# new_esplay.net
KiCad netlist of a schematic drawn in EAGLE
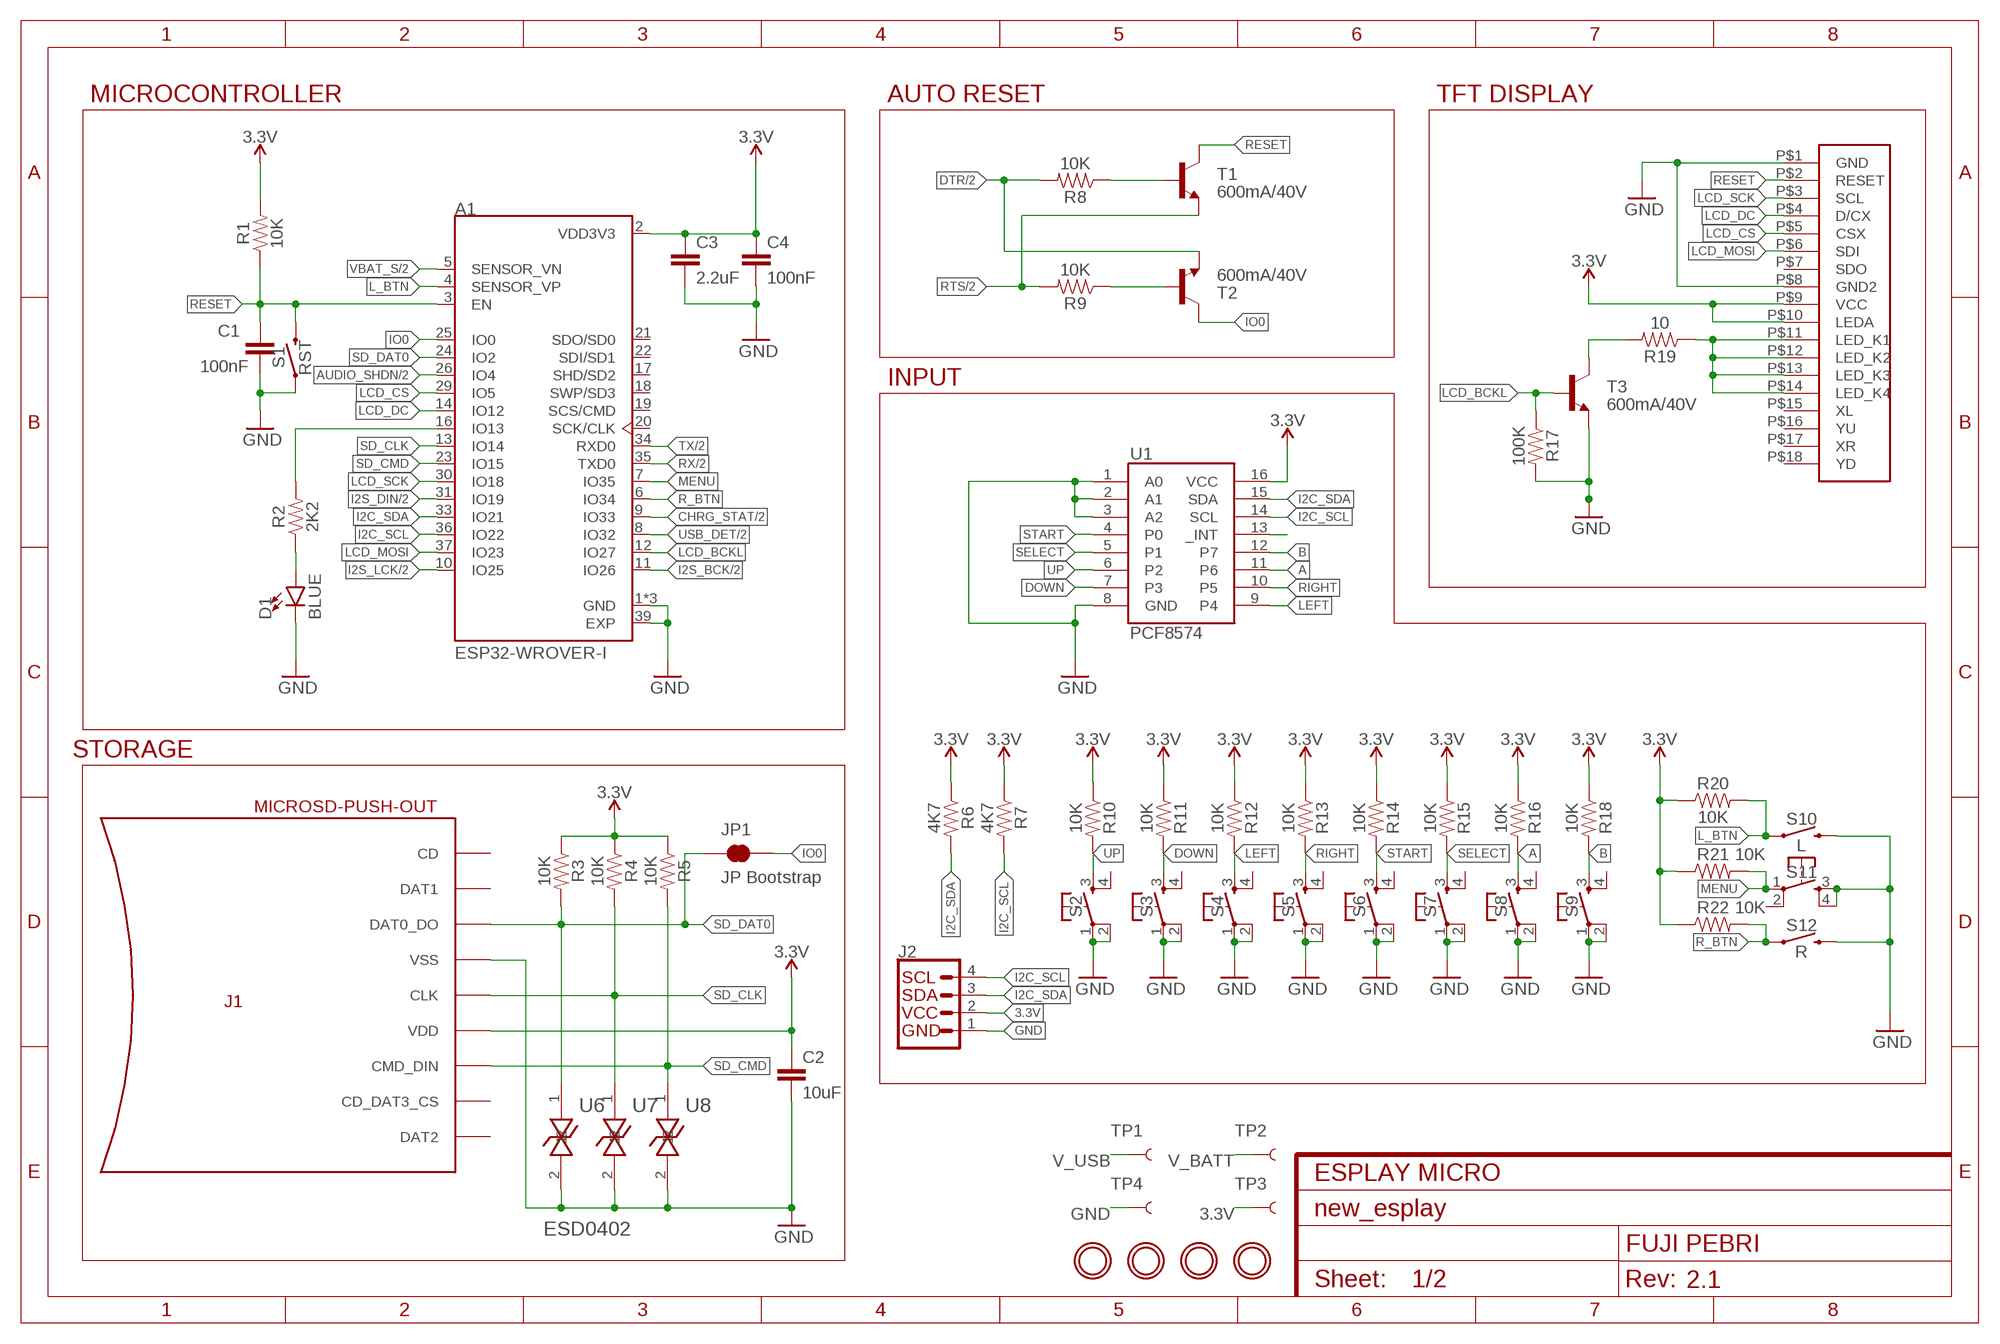
[diagram p0: schematic, sheet 1]
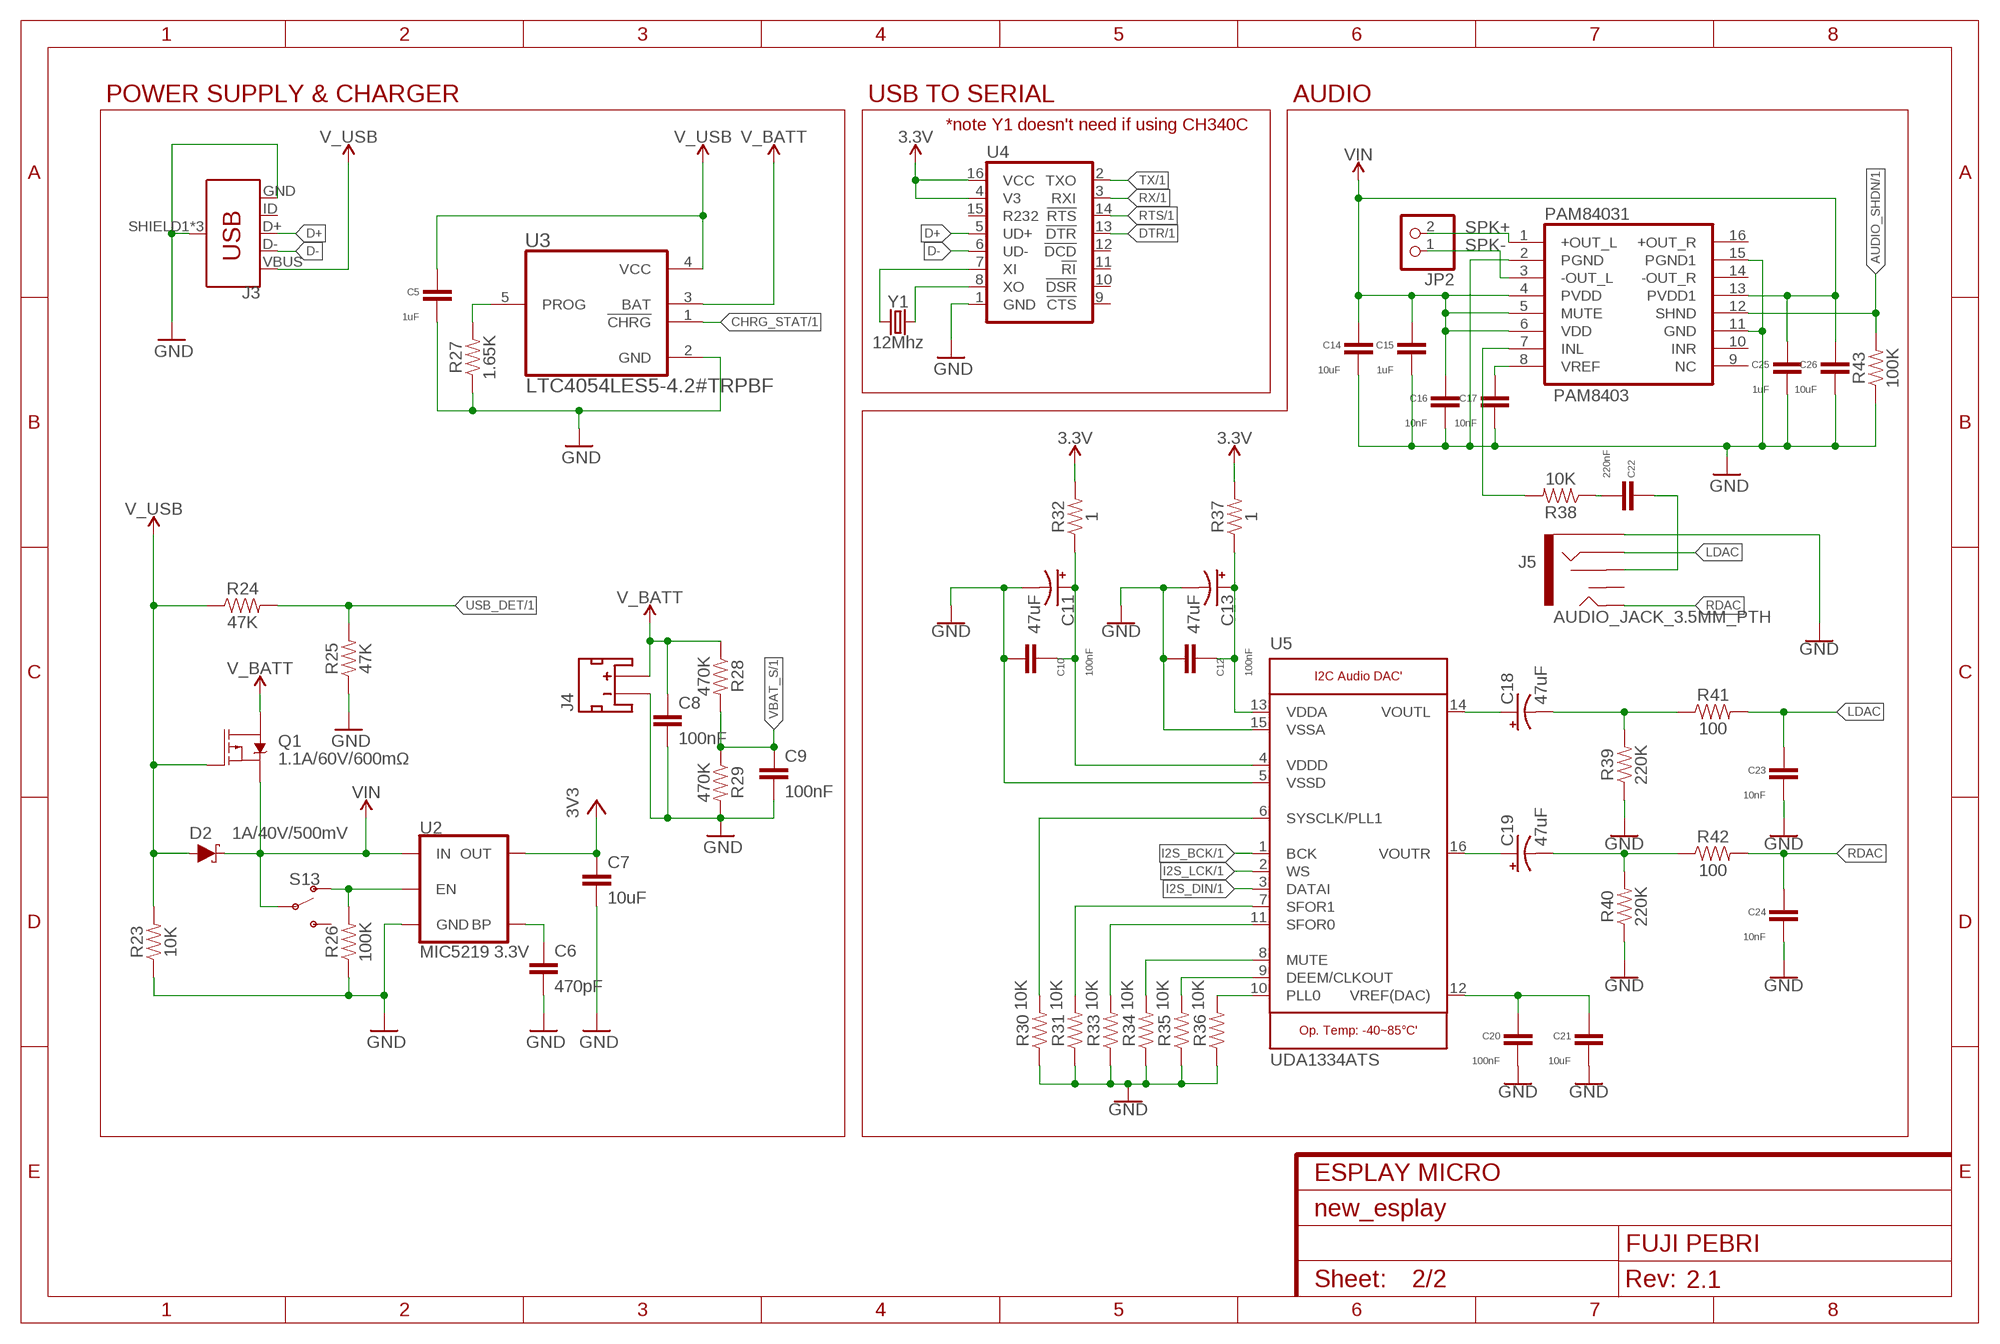
[diagram p1: schematic, sheet 2]

(export (version "E")
  (design (tool "Eeschema 10.0.6"))
  (components
    (comp (ref "A1")
      (value "ESP32-WROVER-I")
      (footprint "eagle-import:XCVR_ESP32-WROVER-I")
      (fields (field (name "MF") "Espressif Systems"))
      (libsource (lib "eagle-import") (part "ESP32-WROVER-I"))
    )
    (comp (ref "C1")
      (value "100nF")
      (footprint "eagle-import:0805")
      (libsource (lib "eagle-import") (part "2.2UF-0805-25V-(+80/-20%)"))
    )
    (comp (ref "C2")
      (value "10uF")
      (footprint "eagle-import:0805")
      (libsource (lib "eagle-import") (part "2.2UF-0805-25V-(+80/-20%)"))
    )
    (comp (ref "C3")
      (value "2.2uF")
      (footprint "eagle-import:0805")
      (libsource (lib "eagle-import") (part "2.2UF-0805-25V-(+80/-20%)"))
    )
    (comp (ref "C4")
      (value "100nF")
      (footprint "eagle-import:0805")
      (libsource (lib "eagle-import") (part "2.2UF-0805-25V-(+80/-20%)"))
    )
    (comp (ref "D1")
      (value "BLUE")
      (footprint "eagle-import:LED-0603")
      (libsource (lib "eagle-import") (part "LED-BLUE0603"))
    )
    (comp (ref "H1")
      (value "MICROBUILDER_MOUNTINGHOLE3.0THIN")
      (footprint "eagle-import:MICROBUILDER_MOUNTINGHOLE_3.0_PLATEDTHIN")
      (libsource (lib "eagle-import") (part "MICROBUILDER_MOUNTINGHOLE3.0THIN"))
    )
    (comp (ref "H2")
      (value "MICROBUILDER_MOUNTINGHOLE3.0THIN")
      (footprint "eagle-import:MICROBUILDER_MOUNTINGHOLE_3.0_PLATEDTHIN")
      (libsource (lib "eagle-import") (part "MICROBUILDER_MOUNTINGHOLE3.0THIN"))
    )
    (comp (ref "H3")
      (value "MICROBUILDER_MOUNTINGHOLE3.0THIN")
      (footprint "eagle-import:MICROBUILDER_MOUNTINGHOLE_3.0_PLATEDTHIN")
      (libsource (lib "eagle-import") (part "MICROBUILDER_MOUNTINGHOLE3.0THIN"))
    )
    (comp (ref "H4")
      (value "MICROBUILDER_MOUNTINGHOLE3.0THIN")
      (footprint "eagle-import:MICROBUILDER_MOUNTINGHOLE_3.0_PLATEDTHIN")
      (libsource (lib "eagle-import") (part "MICROBUILDER_MOUNTINGHOLE3.0THIN"))
    )
    (comp (ref "J1")
      (value "MICROSD-PUSH-OUT")
      (footprint "eagle-import:MICROSD-PUSH-OUT")
      (libsource (lib "eagle-import") (part "MICROSD-PUSH-OUT"))
    )
    (comp (ref "J2")
      (value "QWIIC_CONNECTORJS-1MM")
      (footprint "eagle-import:1X04_1MM_RA")
      (libsource (lib "eagle-import") (part "QWIIC_CONNECTORJS-1MM"))
    )
    (comp (ref "JP1")
      (value "JP Bootstrap")
      (footprint "eagle-import:SMT-JUMPER_2_NC_TRACE_NO-SILK")
      (libsource (lib "eagle-import") (part "JUMPER-SMT_2_NC_TRACE_NO-SILK"))
    )
    (comp (ref "LCD1")
      (value "ILI9341-2.4")
      (footprint "eagle-import:ILI9341-2.4")
      (libsource (lib "eagle-import") (part "ILI9341-2.4"))
    )
    (comp (ref "R1")
      (value "10K")
      (footprint "eagle-import:0805")
      (libsource (lib "eagle-import") (part "0.22OHM-0805-1/4W-1%"))
    )
    (comp (ref "R2")
      (value "2K2")
      (footprint "eagle-import:0805")
      (libsource (lib "eagle-import") (part "0.22OHM-0805-1/4W-1%"))
    )
    (comp (ref "R3")
      (value "10K")
      (footprint "eagle-import:0805")
      (libsource (lib "eagle-import") (part "0.22OHM-0805-1/4W-1%"))
    )
    (comp (ref "R4")
      (value "10K")
      (footprint "eagle-import:0805")
      (libsource (lib "eagle-import") (part "0.22OHM-0805-1/4W-1%"))
    )
    (comp (ref "R5")
      (value "10K")
      (footprint "eagle-import:0805")
      (libsource (lib "eagle-import") (part "0.22OHM-0805-1/4W-1%"))
    )
    (comp (ref "R6")
      (value "4K7")
      (footprint "eagle-import:0805")
      (libsource (lib "eagle-import") (part "0.22OHM-0805-1/4W-1%"))
    )
    (comp (ref "R7")
      (value "4K7")
      (footprint "eagle-import:0805")
      (libsource (lib "eagle-import") (part "0.22OHM-0805-1/4W-1%"))
    )
    (comp (ref "R8")
      (value "10K")
      (footprint "eagle-import:0805")
      (libsource (lib "eagle-import") (part "0.22OHM-0805-1/4W-1%"))
    )
    (comp (ref "R9")
      (value "10K")
      (footprint "eagle-import:0805")
      (libsource (lib "eagle-import") (part "0.22OHM-0805-1/4W-1%"))
    )
    (comp (ref "R10")
      (value "10K")
      (footprint "eagle-import:0805")
      (libsource (lib "eagle-import") (part "0.22OHM-0805-1/4W-1%"))
    )
    (comp (ref "R11")
      (value "10K")
      (footprint "eagle-import:0805")
      (libsource (lib "eagle-import") (part "0.22OHM-0805-1/4W-1%"))
    )
    (comp (ref "R12")
      (value "10K")
      (footprint "eagle-import:0805")
      (libsource (lib "eagle-import") (part "0.22OHM-0805-1/4W-1%"))
    )
    (comp (ref "R13")
      (value "10K")
      (footprint "eagle-import:0805")
      (libsource (lib "eagle-import") (part "0.22OHM-0805-1/4W-1%"))
    )
    (comp (ref "R14")
      (value "10K")
      (footprint "eagle-import:0805")
      (libsource (lib "eagle-import") (part "0.22OHM-0805-1/4W-1%"))
    )
    (comp (ref "R15")
      (value "10K")
      (footprint "eagle-import:0805")
      (libsource (lib "eagle-import") (part "0.22OHM-0805-1/4W-1%"))
    )
    (comp (ref "R16")
      (value "10K")
      (footprint "eagle-import:0805")
      (libsource (lib "eagle-import") (part "0.22OHM-0805-1/4W-1%"))
    )
    (comp (ref "R17")
      (value "100K")
      (footprint "eagle-import:0805")
      (libsource (lib "eagle-import") (part "0.22OHM-0805-1/4W-1%"))
    )
    (comp (ref "R18")
      (value "10K")
      (footprint "eagle-import:0805")
      (libsource (lib "eagle-import") (part "0.22OHM-0805-1/4W-1%"))
    )
    (comp (ref "R19")
      (value "10")
      (footprint "eagle-import:0805")
      (libsource (lib "eagle-import") (part "0.22OHM-0805-1/4W-1%"))
    )
    (comp (ref "R20")
      (value "10K")
      (footprint "eagle-import:0805")
      (libsource (lib "eagle-import") (part "0.22OHM-0805-1/4W-1%"))
    )
    (comp (ref "R21")
      (value "10K")
      (footprint "eagle-import:0805")
      (libsource (lib "eagle-import") (part "0.22OHM-0805-1/4W-1%"))
    )
    (comp (ref "R22")
      (value "10K")
      (footprint "eagle-import:0805")
      (libsource (lib "eagle-import") (part "0.22OHM-0805-1/4W-1%"))
    )
    (comp (ref "S1")
      (value "RST")
      (footprint "eagle-import:TACTILE_SWITCH_SMD_4.6X2.8MM")
      (libsource (lib "eagle-import") (part "MOMENTARY-SWITCH-SPST-SMD-4.6X2.8MM"))
    )
    (comp (ref "S2")
      (value "MOMENTARY-SWITCH-SPST-2-SMD-5.2MM")
      (footprint "eagle-import:TACTILE_SWITCH_SMD_5.2MM")
      (libsource (lib "eagle-import") (part "MOMENTARY-SWITCH-SPST-2-SMD-5.2MM"))
    )
    (comp (ref "S3")
      (value "MOMENTARY-SWITCH-SPST-2-SMD-5.2MM")
      (footprint "eagle-import:TACTILE_SWITCH_SMD_5.2MM")
      (libsource (lib "eagle-import") (part "MOMENTARY-SWITCH-SPST-2-SMD-5.2MM"))
    )
    (comp (ref "S4")
      (value "MOMENTARY-SWITCH-SPST-2-SMD-5.2MM")
      (footprint "eagle-import:TACTILE_SWITCH_SMD_5.2MM")
      (libsource (lib "eagle-import") (part "MOMENTARY-SWITCH-SPST-2-SMD-5.2MM"))
    )
    (comp (ref "S5")
      (value "MOMENTARY-SWITCH-SPST-2-SMD-5.2MM")
      (footprint "eagle-import:TACTILE_SWITCH_SMD_5.2MM")
      (libsource (lib "eagle-import") (part "MOMENTARY-SWITCH-SPST-2-SMD-5.2MM"))
    )
    (comp (ref "S6")
      (value "MOMENTARY-SWITCH-SPST-2-SMD-5.2MM")
      (footprint "eagle-import:TACTILE_SWITCH_SMD_5.2MM")
      (libsource (lib "eagle-import") (part "MOMENTARY-SWITCH-SPST-2-SMD-5.2MM"))
    )
    (comp (ref "S7")
      (value "MOMENTARY-SWITCH-SPST-2-SMD-5.2MM")
      (footprint "eagle-import:TACTILE_SWITCH_SMD_5.2MM")
      (libsource (lib "eagle-import") (part "MOMENTARY-SWITCH-SPST-2-SMD-5.2MM"))
    )
    (comp (ref "S8")
      (value "MOMENTARY-SWITCH-SPST-2-SMD-5.2MM")
      (footprint "eagle-import:TACTILE_SWITCH_SMD_5.2MM")
      (libsource (lib "eagle-import") (part "MOMENTARY-SWITCH-SPST-2-SMD-5.2MM"))
    )
    (comp (ref "S9")
      (value "MOMENTARY-SWITCH-SPST-2-SMD-5.2MM")
      (footprint "eagle-import:TACTILE_SWITCH_SMD_5.2MM")
      (libsource (lib "eagle-import") (part "MOMENTARY-SWITCH-SPST-2-SMD-5.2MM"))
    )
    (comp (ref "S10")
      (value "L")
      (footprint "eagle-import:TACTILE_SWITCH_PTH_RIGHT_ANGLE_KIT")
      (libsource (lib "eagle-import") (part "MOMENTARY-SWITCH-SPST-PTH-RIGHT-ANGLE-KIT"))
    )
    (comp (ref "S11")
      (value "MOMENTARY-SWITCH-SPST-2-SMD-5.2MM")
      (footprint "eagle-import:TACTILE_SWITCH_SMD_5.2MM")
      (libsource (lib "eagle-import") (part "MOMENTARY-SWITCH-SPST-2-SMD-5.2MM"))
    )
    (comp (ref "S12")
      (value "R")
      (footprint "eagle-import:TACTILE_SWITCH_PTH_RIGHT_ANGLE_KIT")
      (libsource (lib "eagle-import") (part "MOMENTARY-SWITCH-SPST-PTH-RIGHT-ANGLE-KIT"))
    )
    (comp (ref "T1")
      (value "600mA/40V")
      (footprint "eagle-import:SOT23-3")
      (libsource (lib "eagle-import") (part "TRANS_NPN-MMBT2222AL"))
    )
    (comp (ref "T2")
      (value "600mA/40V")
      (footprint "eagle-import:SOT23-3")
      (libsource (lib "eagle-import") (part "TRANS_NPN-MMBT2222AL"))
    )
    (comp (ref "T3")
      (value "600mA/40V")
      (footprint "eagle-import:SOT23-3")
      (libsource (lib "eagle-import") (part "TRANS_NPN-MMBT2222AL"))
    )
    (comp (ref "TP1")
      (value "TEST-POINT3")
      (footprint "eagle-import:PAD.03X.03")
      (libsource (lib "eagle-import") (part "TEST-POINT3"))
    )
    (comp (ref "TP2")
      (value "TEST-POINT3")
      (footprint "eagle-import:PAD.03X.03")
      (libsource (lib "eagle-import") (part "TEST-POINT3"))
    )
    (comp (ref "TP3")
      (value "TEST-POINT3")
      (footprint "eagle-import:PAD.03X.03")
      (libsource (lib "eagle-import") (part "TEST-POINT3"))
    )
    (comp (ref "TP4")
      (value "TEST-POINT3")
      (footprint "eagle-import:PAD.03X.03")
      (libsource (lib "eagle-import") (part "TEST-POINT3"))
    )
    (comp (ref "U1")
      (value "PCF8574")
      (footprint "eagle-import:SO16")
      (fields (field (name "MF") "Texas Instruments"))
      (libsource (lib "eagle-import") (part "PCF8574"))
    )
    (comp (ref "U6")
      (value "ESD0402")
      (footprint "eagle-import:ESD0402")
      (libsource (lib "eagle-import") (part "ESD0402"))
    )
    (comp (ref "U7")
      (value "ESD0402")
      (footprint "eagle-import:ESD0402")
      (libsource (lib "eagle-import") (part "ESD0402"))
    )
    (comp (ref "U8")
      (value "ESD0402")
      (footprint "eagle-import:ESD0402")
      (libsource (lib "eagle-import") (part "ESD0402"))
    )
    (comp (ref "C5")
      (value "1uF")
      (footprint "eagle-import:0805")
      (libsource (lib "eagle-import") (part "2.2UF-0805-25V-(+80/-20%)"))
    )
    (comp (ref "C6")
      (value "470pF")
      (footprint "eagle-import:0805")
      (libsource (lib "eagle-import") (part "2.2UF-0805-25V-(+80/-20%)"))
    )
    (comp (ref "C7")
      (value "10uF")
      (footprint "eagle-import:0805")
      (libsource (lib "eagle-import") (part "2.2UF-0805-25V-(+80/-20%)"))
    )
    (comp (ref "C8")
      (value "100nF")
      (footprint "eagle-import:0805")
      (libsource (lib "eagle-import") (part "2.2UF-0805-25V-(+80/-20%)"))
    )
    (comp (ref "C9")
      (value "100nF")
      (footprint "eagle-import:0805")
      (libsource (lib "eagle-import") (part "2.2UF-0805-25V-(+80/-20%)"))
    )
    (comp (ref "C10")
      (value "100nF")
      (footprint "eagle-import:0805")
      (libsource (lib "eagle-import") (part "2.2UF-0805-25V-(+80/-20%)"))
    )
    (comp (ref "C11")
      (value "47uF")
      (footprint "eagle-import:EIA3528")
      (libsource (lib "eagle-import") (part "47UF-POLAR-EIA3528-10V-10%"))
    )
    (comp (ref "C12")
      (value "100nF")
      (footprint "eagle-import:0805")
      (libsource (lib "eagle-import") (part "2.2UF-0805-25V-(+80/-20%)"))
    )
    (comp (ref "C13")
      (value "47uF")
      (footprint "eagle-import:EIA3528")
      (libsource (lib "eagle-import") (part "47UF-POLAR-EIA3528-10V-10%"))
    )
    (comp (ref "C14")
      (value "10uF")
      (footprint "eagle-import:0805")
      (libsource (lib "eagle-import") (part "2.2UF-0805-25V-(+80/-20%)"))
    )
    (comp (ref "C15")
      (value "1uF")
      (footprint "eagle-import:0805")
      (libsource (lib "eagle-import") (part "2.2UF-0805-25V-(+80/-20%)"))
    )
    (comp (ref "C16")
      (value "10nF")
      (footprint "eagle-import:0805")
      (libsource (lib "eagle-import") (part "2.2UF-0805-25V-(+80/-20%)"))
    )
    (comp (ref "C17")
      (value "10nF")
      (footprint "eagle-import:0805")
      (libsource (lib "eagle-import") (part "2.2UF-0805-25V-(+80/-20%)"))
    )
    (comp (ref "C18")
      (value "47uF")
      (footprint "eagle-import:EIA3528")
      (libsource (lib "eagle-import") (part "47UF-POLAR-EIA3528-10V-10%"))
    )
    (comp (ref "C19")
      (value "47uF")
      (footprint "eagle-import:EIA3528")
      (libsource (lib "eagle-import") (part "47UF-POLAR-EIA3528-10V-10%"))
    )
    (comp (ref "C20")
      (value "100nF")
      (footprint "eagle-import:0805")
      (libsource (lib "eagle-import") (part "2.2UF-0805-25V-(+80/-20%)"))
    )
    (comp (ref "C21")
      (value "10uF")
      (footprint "eagle-import:0805")
      (libsource (lib "eagle-import") (part "2.2UF-0805-25V-(+80/-20%)"))
    )
    (comp (ref "C22")
      (value "220nF")
      (footprint "eagle-import:0805")
      (libsource (lib "eagle-import") (part "2.2UF-0805-25V-(+80/-20%)"))
    )
    (comp (ref "C23")
      (value "10nF")
      (footprint "eagle-import:0805")
      (libsource (lib "eagle-import") (part "2.2UF-0805-25V-(+80/-20%)"))
    )
    (comp (ref "C24")
      (value "10nF")
      (footprint "eagle-import:0805")
      (libsource (lib "eagle-import") (part "2.2UF-0805-25V-(+80/-20%)"))
    )
    (comp (ref "C25")
      (value "1uF")
      (footprint "eagle-import:0805")
      (libsource (lib "eagle-import") (part "2.2UF-0805-25V-(+80/-20%)"))
    )
    (comp (ref "C26")
      (value "10uF")
      (footprint "eagle-import:0805")
      (libsource (lib "eagle-import") (part "2.2UF-0805-25V-(+80/-20%)"))
    )
    (comp (ref "D2")
      (value "1A/40V/500mV")
      (footprint "eagle-import:SMA-DIODE")
      (libsource (lib "eagle-import") (part "DIODE-SCHOTTKY-SS14"))
    )
    (comp (ref "J3")
      (value "USB_MICRO-B_FEMALE-SMT")
      (footprint "eagle-import:USB-B-MICRO-SMD")
      (libsource (lib "eagle-import") (part "USB_MICRO-B_FEMALE-SMT"))
    )
    (comp (ref "J4")
      (value "JST_2MM_MALE")
      (footprint "eagle-import:JST-2-SMD")
      (libsource (lib "eagle-import") (part "JST_2MM_MALE"))
    )
    (comp (ref "J5")
      (value "AUDIO_JACK_3.5MM_PTH")
      (footprint "eagle-import:AUDIO-JACK")
      (libsource (lib "eagle-import") (part "AUDIO_JACK_3.5MM_PTH"))
    )
    (comp (ref "JP2")
      (value "PINHD-1X2_2.00")
      (footprint "eagle-import:1X02M")
      (libsource (lib "eagle-import") (part "PINHD-1X2_2.00"))
    )
    (comp (ref "PAM84031")
      (value "PAM8403")
      (footprint "eagle-import:SOP-16")
      (libsource (lib "eagle-import") (part "PAM8403"))
    )
    (comp (ref "Q1")
      (value "1.1A/60V/600mΩ")
      (footprint "eagle-import:SOT23-3")
      (libsource (lib "eagle-import") (part "MOSFET_PCH-SI2309DS"))
    )
    (comp (ref "R23")
      (value "10K")
      (footprint "eagle-import:0805")
      (libsource (lib "eagle-import") (part "0.22OHM-0805-1/4W-1%"))
    )
    (comp (ref "R24")
      (value "47K")
      (footprint "eagle-import:0805")
      (libsource (lib "eagle-import") (part "0.22OHM-0805-1/4W-1%"))
    )
    (comp (ref "R25")
      (value "47K")
      (footprint "eagle-import:0805")
      (libsource (lib "eagle-import") (part "0.22OHM-0805-1/4W-1%"))
    )
    (comp (ref "R26")
      (value "100K")
      (footprint "eagle-import:0805")
      (libsource (lib "eagle-import") (part "0.22OHM-0805-1/4W-1%"))
    )
    (comp (ref "R27")
      (value "1.65K")
      (footprint "eagle-import:0805")
      (libsource (lib "eagle-import") (part "0.3OHM-0805-1/8W-1%"))
    )
    (comp (ref "R28")
      (value "470K")
      (footprint "eagle-import:0805")
      (libsource (lib "eagle-import") (part "0.22OHM-0805-1/4W-1%"))
    )
    (comp (ref "R29")
      (value "470K")
      (footprint "eagle-import:0805")
      (libsource (lib "eagle-import") (part "0.22OHM-0805-1/4W-1%"))
    )
    (comp (ref "R30")
      (value "10K")
      (footprint "eagle-import:0805")
      (libsource (lib "eagle-import") (part "0.3OHM-0805-1/8W-1%"))
    )
    (comp (ref "R31")
      (value "10K")
      (footprint "eagle-import:0805")
      (libsource (lib "eagle-import") (part "0.3OHM-0805-1/8W-1%"))
    )
    (comp (ref "R32")
      (value "1")
      (footprint "eagle-import:0805")
      (libsource (lib "eagle-import") (part "0.3OHM-0805-1/8W-1%"))
    )
    (comp (ref "R33")
      (value "10K")
      (footprint "eagle-import:0805")
      (libsource (lib "eagle-import") (part "0.3OHM-0805-1/8W-1%"))
    )
    (comp (ref "R34")
      (value "10K")
      (footprint "eagle-import:0805")
      (libsource (lib "eagle-import") (part "0.3OHM-0805-1/8W-1%"))
    )
    (comp (ref "R35")
      (value "10K")
      (footprint "eagle-import:0805")
      (libsource (lib "eagle-import") (part "0.3OHM-0805-1/8W-1%"))
    )
    (comp (ref "R36")
      (value "10K")
      (footprint "eagle-import:0805")
      (libsource (lib "eagle-import") (part "0.3OHM-0805-1/8W-1%"))
    )
    (comp (ref "R37")
      (value "1")
      (footprint "eagle-import:0805")
      (libsource (lib "eagle-import") (part "0.3OHM-0805-1/8W-1%"))
    )
    (comp (ref "R38")
      (value "10K")
      (footprint "eagle-import:0805")
      (libsource (lib "eagle-import") (part "0.3OHM-0805-1/8W-1%"))
    )
    (comp (ref "R39")
      (value "220K")
      (footprint "eagle-import:0805")
      (libsource (lib "eagle-import") (part "0.3OHM-0805-1/8W-1%"))
    )
    (comp (ref "R40")
      (value "220K")
      (footprint "eagle-import:0805")
      (libsource (lib "eagle-import") (part "0.3OHM-0805-1/8W-1%"))
    )
    (comp (ref "R41")
      (value "100")
      (footprint "eagle-import:0805")
      (libsource (lib "eagle-import") (part "0.3OHM-0805-1/8W-1%"))
    )
    (comp (ref "R42")
      (value "100")
      (footprint "eagle-import:0805")
      (libsource (lib "eagle-import") (part "0.3OHM-0805-1/8W-1%"))
    )
    (comp (ref "R43")
      (value "100K")
      (footprint "eagle-import:0805")
      (libsource (lib "eagle-import") (part "0.3OHM-0805-1/8W-1%"))
    )
    (comp (ref "S13")
      (value "SWITCH-SPDT-SMD-RIGHT-ANGLE")
      (footprint "eagle-import:SWITCH_SPST_SMD_A")
      (libsource (lib "eagle-import") (part "SWITCH-SPDT-SMD-RIGHT-ANGLE"))
    )
    (comp (ref "U2")
      (value "MIC5219 3.3V")
      (footprint "eagle-import:SOT23-5")
      (libsource (lib "eagle-import") (part "V_REG_MIC52193.3V"))
    )
    (comp (ref "U3")
      (value "LTC4054LES5-4.2#TRPBF")
      (footprint "eagle-import:SOT95P280X100-5N")
      (fields
        (field (name "DIGI-KEY_PART_NUMBER") "LTC4054LES5-4.2#TRPBFCT-ND")
        (field (name "MF") "Linear Technology/Analog")
      )
      (libsource (lib "eagle-import") (part "LTC4054LES5-4.2#TRPBF"))
    )
    (comp (ref "U4")
      (value "CH340G")
      (footprint "eagle-import:SO016")
      (libsource (lib "eagle-import") (part "CH340GSMD"))
    )
    (comp (ref "U5")
      (value "UDA1334ATS")
      (footprint "eagle-import:MICROBUILDER_SSOP16_4.4MM")
      (libsource (lib "eagle-import") (part "MICROBUILDER_AUDIO_I2S_UDA1334{dblquote}{dblquote}"))
    )
    (comp (ref "Y1")
      (value "12Mhz")
      (footprint "eagle-import:CRYSTAL-SMD-5X3.2-4PAD")
      (libsource (lib "eagle-import") (part "CRYSTALSMD-5X3.2-4PAD"))
    )
  )
  (nets
    (net (code "1") (name "3.3V") (class "Default")
      (node (ref "A1") (pin "2") (pinfunction "VDD3V3_2") (pintype "power_in"))
      (node (ref "C2") (pin "1") (pinfunction "1_1") (pintype "passive"))
      (node (ref "C3") (pin "1") (pinfunction "1_1") (pintype "passive"))
      (node (ref "C4") (pin "1") (pinfunction "1_1") (pintype "passive"))
      (node (ref "C7") (pin "1") (pinfunction "1_1") (pintype "passive"))
      (node (ref "J1") (pin "4") (pinfunction "VDD_4") (pintype "bidirectional"))
      (node (ref "J2") (pin "2") (pinfunction "2_2") (pintype "power_in"))
      (node (ref "LCD1") (pin "P$10") (pinfunction "LEDA_P$10") (pintype "bidirectional"))
      (node (ref "LCD1") (pin "P$9") (pinfunction "VCC_P$9") (pintype "bidirectional"))
      (node (ref "R1") (pin "2") (pinfunction "2_2") (pintype "passive"))
      (node (ref "R10") (pin "1") (pinfunction "1_1") (pintype "passive"))
      (node (ref "R11") (pin "1") (pinfunction "1_1") (pintype "passive"))
      (node (ref "R12") (pin "1") (pinfunction "1_1") (pintype "passive"))
      (node (ref "R13") (pin "1") (pinfunction "1_1") (pintype "passive"))
      (node (ref "R14") (pin "1") (pinfunction "1_1") (pintype "passive"))
      (node (ref "R15") (pin "1") (pinfunction "1_1") (pintype "passive"))
      (node (ref "R16") (pin "1") (pinfunction "1_1") (pintype "passive"))
      (node (ref "R18") (pin "1") (pinfunction "1_1") (pintype "passive"))
      (node (ref "R20") (pin "1") (pinfunction "1_1") (pintype "passive"))
      (node (ref "R21") (pin "1") (pinfunction "1_1") (pintype "passive"))
      (node (ref "R22") (pin "1") (pinfunction "1_1") (pintype "passive"))
      (node (ref "R3") (pin "1") (pinfunction "1_1") (pintype "passive"))
      (node (ref "R32") (pin "2") (pinfunction "2_2") (pintype "passive"))
      (node (ref "R37") (pin "2") (pinfunction "2_2") (pintype "passive"))
      (node (ref "R4") (pin "1") (pinfunction "1_1") (pintype "passive"))
      (node (ref "R5") (pin "1") (pinfunction "1_1") (pintype "passive"))
      (node (ref "R6") (pin "1") (pinfunction "1_1") (pintype "passive"))
      (node (ref "R7") (pin "1") (pinfunction "1_1") (pintype "passive"))
      (node (ref "TP3") (pin "P$1") (pinfunction "1_P$1") (pintype "bidirectional"))
      (node (ref "U1") (pin "16") (pinfunction "VCC_16") (pintype "bidirectional"))
      (node (ref "U2") (pin "5") (pinfunction "OUT_5") (pintype "passive"))
      (node (ref "U4") (pin "16") (pinfunction "VCC_16") (pintype "bidirectional"))
      (node (ref "U4") (pin "4") (pinfunction "V3_4") (pintype "bidirectional"))
    )
    (net (code "2") (name "A") (class "Default")
      (node (ref "R16") (pin "2") (pinfunction "2_2") (pintype "passive"))
      (node (ref "S8") (pin "3") (pinfunction "3_3") (pintype "passive"))
      (node (ref "U1") (pin "11") (pinfunction "P6_11") (pintype "bidirectional"))
    )
    (net (code "3") (name "AUDIO_SHDN") (class "Default")
      (node (ref "A1") (pin "26") (pinfunction "IO4_26") (pintype "bidirectional"))
      (node (ref "PAM84031") (pin "12") (pinfunction "SHND_12") (pintype "output"))
      (node (ref "R43") (pin "2") (pinfunction "2_2") (pintype "passive"))
    )
    (net (code "4") (name "B") (class "Default")
      (node (ref "R18") (pin "2") (pinfunction "2_2") (pintype "passive"))
      (node (ref "S9") (pin "3") (pinfunction "3_3") (pintype "passive"))
      (node (ref "U1") (pin "12") (pinfunction "P7_12") (pintype "bidirectional"))
    )
    (net (code "5") (name "CHRG_STAT") (class "Default")
      (node (ref "A1") (pin "9") (pinfunction "IO33_9") (pintype "bidirectional"))
      (node (ref "U3") (pin "1") (pinfunction "~{CHRG}_1") (pintype "output"))
    )
    (net (code "6") (name "D+") (class "Default")
      (node (ref "J3") (pin "D+") (pinfunction "D+_D+") (pintype "bidirectional"))
      (node (ref "U4") (pin "5") (pinfunction "UD+_5") (pintype "bidirectional"))
    )
    (net (code "7") (name "D-") (class "Default")
      (node (ref "J3") (pin "D-") (pinfunction "D-_D-") (pintype "bidirectional"))
      (node (ref "U4") (pin "6") (pinfunction "UD-_6") (pintype "bidirectional"))
    )
    (net (code "8") (name "DOWN") (class "Default")
      (node (ref "R11") (pin "2") (pinfunction "2_2") (pintype "passive"))
      (node (ref "S3") (pin "3") (pinfunction "3_3") (pintype "passive"))
      (node (ref "U1") (pin "7") (pinfunction "P3_7") (pintype "bidirectional"))
    )
    (net (code "9") (name "DTR") (class "Default")
      (node (ref "R8") (pin "2") (pinfunction "2_2") (pintype "passive"))
      (node (ref "T2") (pin "2") (pinfunction "E_2") (pintype "passive"))
      (node (ref "U4") (pin "13") (pinfunction "~{DTR}_13") (pintype "bidirectional"))
    )
    (net (code "10") (name "GND") (class "Default")
      (node (ref "A1") (pin "1") (pinfunction "GND_1") (pintype "power_in"))
      (node (ref "A1") (pin "15") (pinfunction "GND_15") (pintype "power_in"))
      (node (ref "A1") (pin "38") (pinfunction "GND_38") (pintype "power_in"))
      (node (ref "A1") (pin "39") (pinfunction "EXP_39") (pintype "power_in"))
      (node (ref "C1") (pin "2") (pinfunction "2_2") (pintype "passive"))
      (node (ref "C10") (pin "1") (pinfunction "1_1") (pintype "passive"))
      (node (ref "C11") (pin "C") (pinfunction "-_C") (pintype "passive"))
      (node (ref "C12") (pin "1") (pinfunction "1_1") (pintype "passive"))
      (node (ref "C13") (pin "C") (pinfunction "-_C") (pintype "passive"))
      (node (ref "C14") (pin "1") (pinfunction "1_1") (pintype "passive"))
      (node (ref "C15") (pin "1") (pinfunction "1_1") (pintype "passive"))
      (node (ref "C16") (pin "1") (pinfunction "1_1") (pintype "passive"))
      (node (ref "C17") (pin "1") (pinfunction "1_1") (pintype "passive"))
      (node (ref "C2") (pin "2") (pinfunction "2_2") (pintype "passive"))
      (node (ref "C20") (pin "1") (pinfunction "1_1") (pintype "passive"))
      (node (ref "C21") (pin "1") (pinfunction "1_1") (pintype "passive"))
      (node (ref "C23") (pin "1") (pinfunction "1_1") (pintype "passive"))
      (node (ref "C24") (pin "1") (pinfunction "1_1") (pintype "passive"))
      (node (ref "C25") (pin "1") (pinfunction "1_1") (pintype "passive"))
      (node (ref "C26") (pin "1") (pinfunction "1_1") (pintype "passive"))
      (node (ref "C3") (pin "2") (pinfunction "2_2") (pintype "passive"))
      (node (ref "C4") (pin "2") (pinfunction "2_2") (pintype "passive"))
      (node (ref "C5") (pin "1") (pinfunction "1_1") (pintype "passive"))
      (node (ref "C6") (pin "2") (pinfunction "2_2") (pintype "passive"))
      (node (ref "C7") (pin "2") (pinfunction "2_2") (pintype "passive"))
      (node (ref "C8") (pin "2") (pinfunction "2_2") (pintype "passive"))
      (node (ref "C9") (pin "2") (pinfunction "2_2") (pintype "passive"))
      (node (ref "D1") (pin "C") (pinfunction "C_C") (pintype "passive"))
      (node (ref "J1") (pin "6") (pinfunction "VSS_6") (pintype "bidirectional"))
      (node (ref "J1") (pin "G1") (pinfunction "VSS_G1") (pintype "bidirectional"))
      (node (ref "J1") (pin "G2") (pinfunction "VSS_G2") (pintype "bidirectional"))
      (node (ref "J1") (pin "G3") (pinfunction "VSS_G3") (pintype "bidirectional"))
      (node (ref "J1") (pin "G4") (pinfunction "VSS_G4") (pintype "bidirectional"))
      (node (ref "J2") (pin "1") (pinfunction "1_1") (pintype "power_in"))
      (node (ref "J3") (pin "GND") (pinfunction "GND_GND") (pintype "power_in"))
      (node (ref "J3") (pin "SHIELD1") (pinfunction "SHIELD_SHIELD1") (pintype "bidirectional"))
      (node (ref "J3") (pin "SHIELD2") (pinfunction "SHIELD_SHIELD2") (pintype "bidirectional"))
      (node (ref "J3") (pin "SHIELD3") (pinfunction "SHIELD_SHIELD3") (pintype "bidirectional"))
      (node (ref "J4") (pin "1") (pinfunction "-_1") (pintype "bidirectional"))
      (node (ref "J5") (pin "SLEEVE") (pinfunction "SLEEVE_SLEEVE") (pintype "bidirectional"))
      (node (ref "LCD1") (pin "P$1") (pinfunction "GND_P$1") (pintype "bidirectional"))
      (node (ref "LCD1") (pin "P$8") (pinfunction "GND2_P$8") (pintype "bidirectional"))
      (node (ref "PAM84031") (pin "11") (pinfunction "GND_11") (pintype "output"))
      (node (ref "PAM84031") (pin "15") (pinfunction "PGND1_15") (pintype "output"))
      (node (ref "PAM84031") (pin "2") (pinfunction "PGND_2") (pintype "input"))
      (node (ref "R17") (pin "2") (pinfunction "2_2") (pintype "passive"))
      (node (ref "R23") (pin "1") (pinfunction "1_1") (pintype "passive"))
      (node (ref "R25") (pin "1") (pinfunction "1_1") (pintype "passive"))
      (node (ref "R26") (pin "1") (pinfunction "1_1") (pintype "passive"))
      (node (ref "R27") (pin "1") (pinfunction "1_1") (pintype "passive"))
      (node (ref "R29") (pin "2") (pinfunction "2_2") (pintype "passive"))
      (node (ref "R30") (pin "1") (pinfunction "1_1") (pintype "passive"))
      (node (ref "R31") (pin "1") (pinfunction "1_1") (pintype "passive"))
      (node (ref "R33") (pin "1") (pinfunction "1_1") (pintype "passive"))
      (node (ref "R34") (pin "1") (pinfunction "1_1") (pintype "passive"))
      (node (ref "R35") (pin "1") (pinfunction "1_1") (pintype "passive"))
      (node (ref "R36") (pin "1") (pinfunction "1_1") (pintype "passive"))
      (node (ref "R39") (pin "1") (pinfunction "1_1") (pintype "passive"))
      (node (ref "R40") (pin "1") (pinfunction "1_1") (pintype "passive"))
      (node (ref "R43") (pin "1") (pinfunction "1_1") (pintype "passive"))
      (node (ref "S1") (pin "1") (pinfunction "1_1") (pintype "passive"))
      (node (ref "S1") (pin "2") (pinfunction "1_2") (pintype "passive"))
      (node (ref "S10") (pin "2") (pinfunction "2_2") (pintype "passive"))
      (node (ref "S11") (pin "3") (pinfunction "3_3") (pintype "passive"))
      (node (ref "S11") (pin "4") (pinfunction "4_4") (pintype "passive"))
      (node (ref "S12") (pin "2") (pinfunction "2_2") (pintype "passive"))
      (node (ref "S2") (pin "1") (pinfunction "1_1") (pintype "passive"))
      (node (ref "S2") (pin "2") (pinfunction "2_2") (pintype "passive"))
      (node (ref "S3") (pin "1") (pinfunction "1_1") (pintype "passive"))
      (node (ref "S3") (pin "2") (pinfunction "2_2") (pintype "passive"))
      (node (ref "S4") (pin "1") (pinfunction "1_1") (pintype "passive"))
      (node (ref "S4") (pin "2") (pinfunction "2_2") (pintype "passive"))
      (node (ref "S5") (pin "1") (pinfunction "1_1") (pintype "passive"))
      (node (ref "S5") (pin "2") (pinfunction "2_2") (pintype "passive"))
      (node (ref "S6") (pin "1") (pinfunction "1_1") (pintype "passive"))
      (node (ref "S6") (pin "2") (pinfunction "2_2") (pintype "passive"))
      (node (ref "S7") (pin "1") (pinfunction "1_1") (pintype "passive"))
      (node (ref "S7") (pin "2") (pinfunction "2_2") (pintype "passive"))
      (node (ref "S8") (pin "1") (pinfunction "1_1") (pintype "passive"))
      (node (ref "S8") (pin "2") (pinfunction "2_2") (pintype "passive"))
      (node (ref "S9") (pin "1") (pinfunction "1_1") (pintype "passive"))
      (node (ref "S9") (pin "2") (pinfunction "2_2") (pintype "passive"))
      (node (ref "T3") (pin "2") (pinfunction "E_2") (pintype "passive"))
      (node (ref "TP4") (pin "P$1") (pinfunction "1_P$1") (pintype "bidirectional"))
      (node (ref "U1") (pin "1") (pinfunction "A0_1") (pintype "bidirectional"))
      (node (ref "U1") (pin "2") (pinfunction "A1_2") (pintype "bidirectional"))
      (node (ref "U1") (pin "3") (pinfunction "A2_3") (pintype "bidirectional"))
      (node (ref "U1") (pin "8") (pinfunction "GND_8") (pintype "bidirectional"))
      (node (ref "U2") (pin "2") (pinfunction "GND_2") (pintype "input"))
      (node (ref "U3") (pin "2") (pinfunction "GND_2") (pintype "power_in"))
      (node (ref "U4") (pin "1") (pinfunction "GND_1") (pintype "bidirectional"))
      (node (ref "U5") (pin "15") (pinfunction "VSSA_15") (pintype "power_in"))
      (node (ref "U5") (pin "5") (pinfunction "VSSD_5") (pintype "power_in"))
      (node (ref "U6") (pin "2") (pinfunction "2_2") (pintype "bidirectional"))
      (node (ref "U7") (pin "2") (pinfunction "2_2") (pintype "bidirectional"))
      (node (ref "U8") (pin "2") (pinfunction "2_2") (pintype "bidirectional"))
    )
    (net (code "11") (name "I2C_SCL") (class "Default")
      (node (ref "A1") (pin "36") (pinfunction "IO22_36") (pintype "bidirectional"))
      (node (ref "J2") (pin "4") (pinfunction "4_4") (pintype "passive"))
      (node (ref "R7") (pin "2") (pinfunction "2_2") (pintype "passive"))
      (node (ref "U1") (pin "14") (pinfunction "SCL_14") (pintype "bidirectional"))
    )
    (net (code "12") (name "I2C_SDA") (class "Default")
      (node (ref "A1") (pin "33") (pinfunction "IO21_33") (pintype "bidirectional"))
      (node (ref "J2") (pin "3") (pinfunction "3_3") (pintype "passive"))
      (node (ref "R6") (pin "2") (pinfunction "2_2") (pintype "passive"))
      (node (ref "U1") (pin "15") (pinfunction "SDA_15") (pintype "bidirectional"))
    )
    (net (code "13") (name "I2S_BCK") (class "Default")
      (node (ref "A1") (pin "11") (pinfunction "IO26_11") (pintype "bidirectional"))
      (node (ref "U5") (pin "1") (pinfunction "BCK_1") (pintype "input"))
    )
    (net (code "14") (name "I2S_DIN") (class "Default")
      (node (ref "A1") (pin "31") (pinfunction "IO19_31") (pintype "bidirectional"))
      (node (ref "U5") (pin "3") (pinfunction "DATAI_3") (pintype "input"))
    )
    (net (code "15") (name "I2S_LCK") (class "Default")
      (node (ref "A1") (pin "10") (pinfunction "IO25_10") (pintype "bidirectional"))
      (node (ref "U5") (pin "2") (pinfunction "WS_2") (pintype "input"))
    )
    (net (code "16") (name "IO0") (class "Default")
      (node (ref "A1") (pin "25") (pinfunction "IO0_25") (pintype "bidirectional"))
      (node (ref "JP1") (pin "2") (pinfunction "2_2") (pintype "passive"))
      (node (ref "T2") (pin "3") (pinfunction "C_3") (pintype "passive"))
    )
    (net (code "17") (name "LCD_BCKL") (class "Default")
      (node (ref "A1") (pin "12") (pinfunction "IO27_12") (pintype "bidirectional"))
      (node (ref "R17") (pin "1") (pinfunction "1_1") (pintype "passive"))
      (node (ref "T3") (pin "1") (pinfunction "B_1") (pintype "passive"))
    )
    (net (code "18") (name "LCD_CS") (class "Default")
      (node (ref "A1") (pin "29") (pinfunction "IO5_29") (pintype "bidirectional"))
      (node (ref "LCD1") (pin "P$5") (pinfunction "CSX_P$5") (pintype "bidirectional"))
    )
    (net (code "19") (name "LCD_DC") (class "Default")
      (node (ref "A1") (pin "14") (pinfunction "IO12_14") (pintype "bidirectional"))
      (node (ref "LCD1") (pin "P$4") (pinfunction "D/CX_P$4") (pintype "bidirectional"))
    )
    (net (code "20") (name "LCD_MOSI") (class "Default")
      (node (ref "A1") (pin "37") (pinfunction "IO23_37") (pintype "bidirectional"))
      (node (ref "LCD1") (pin "P$6") (pinfunction "SDI_P$6") (pintype "bidirectional"))
    )
    (net (code "21") (name "LCD_SCK") (class "Default")
      (node (ref "A1") (pin "30") (pinfunction "IO18_30") (pintype "bidirectional"))
      (node (ref "LCD1") (pin "P$3") (pinfunction "SCL_P$3") (pintype "bidirectional"))
    )
    (net (code "22") (name "LDAC") (class "Default")
      (node (ref "C23") (pin "2") (pinfunction "2_2") (pintype "passive"))
      (node (ref "J5") (pin "RING") (pinfunction "RING_RING") (pintype "bidirectional"))
      (node (ref "R41") (pin "2") (pinfunction "2_2") (pintype "passive"))
    )
    (net (code "23") (name "LEFT") (class "Default")
      (node (ref "R12") (pin "2") (pinfunction "2_2") (pintype "passive"))
      (node (ref "S4") (pin "3") (pinfunction "3_3") (pintype "passive"))
      (node (ref "U1") (pin "9") (pinfunction "P4_9") (pintype "bidirectional"))
    )
    (net (code "24") (name "L_BTN") (class "Default")
      (node (ref "A1") (pin "4") (pinfunction "SENSOR_VP_4") (pintype "input"))
      (node (ref "R20") (pin "2") (pinfunction "2_2") (pintype "passive"))
      (node (ref "S10") (pin "1") (pinfunction "1_1") (pintype "passive"))
    )
    (net (code "25") (name "MENU") (class "Default")
      (node (ref "A1") (pin "7") (pinfunction "IO35_7") (pintype "input"))
      (node (ref "R21") (pin "2") (pinfunction "2_2") (pintype "passive"))
      (node (ref "S11") (pin "1") (pinfunction "1_1") (pintype "passive"))
    )
    (net (code "26") (name "Net-(A1-IO13)") (class "Default")
      (node (ref "A1") (pin "16") (pinfunction "IO13_16") (pintype "bidirectional"))
      (node (ref "R2") (pin "2") (pinfunction "2_2") (pintype "passive"))
    )
    (net (code "27") (name "Net-(C11-+)") (class "Default")
      (node (ref "C10") (pin "2") (pinfunction "2_2") (pintype "passive"))
      (node (ref "C11") (pin "A") (pinfunction "+_A") (pintype "passive"))
      (node (ref "R32") (pin "1") (pinfunction "1_1") (pintype "passive"))
      (node (ref "U5") (pin "4") (pinfunction "VDDD_4") (pintype "power_in"))
    )
    (net (code "28") (name "Net-(C13-+)") (class "Default")
      (node (ref "C12") (pin "2") (pinfunction "2_2") (pintype "passive"))
      (node (ref "C13") (pin "A") (pinfunction "+_A") (pintype "passive"))
      (node (ref "R37") (pin "1") (pinfunction "1_1") (pintype "passive"))
      (node (ref "U5") (pin "13") (pinfunction "VDDA_13") (pintype "power_in"))
    )
    (net (code "29") (name "Net-(C18-+)") (class "Default")
      (node (ref "C18") (pin "A") (pinfunction "+_A") (pintype "passive"))
      (node (ref "U5") (pin "14") (pinfunction "VOUTL_14") (pintype "output"))
    )
    (net (code "30") (name "Net-(C18--)") (class "Default")
      (node (ref "C18") (pin "C") (pinfunction "-_C") (pintype "passive"))
      (node (ref "R39") (pin "2") (pinfunction "2_2") (pintype "passive"))
      (node (ref "R41") (pin "1") (pinfunction "1_1") (pintype "passive"))
    )
    (net (code "31") (name "Net-(C19-+)") (class "Default")
      (node (ref "C19") (pin "A") (pinfunction "+_A") (pintype "passive"))
      (node (ref "U5") (pin "16") (pinfunction "VOUTR_16") (pintype "output"))
    )
    (net (code "32") (name "Net-(C19--)") (class "Default")
      (node (ref "C19") (pin "C") (pinfunction "-_C") (pintype "passive"))
      (node (ref "R40") (pin "2") (pinfunction "2_2") (pintype "passive"))
      (node (ref "R42") (pin "1") (pinfunction "1_1") (pintype "passive"))
    )
    (net (code "33") (name "Net-(C22-Pad1)") (class "Default")
      (node (ref "C22") (pin "1") (pinfunction "1_1") (pintype "passive"))
      (node (ref "R38") (pin "1") (pinfunction "1_1") (pintype "passive"))
    )
    (net (code "34") (name "Net-(C22-Pad2)") (class "Default")
      (node (ref "C22") (pin "2") (pinfunction "2_2") (pintype "passive"))
      (node (ref "J5") (pin "RSH") (pinfunction "RSH_RSH") (pintype "bidirectional"))
    )
    (net (code "35") (name "Net-(D1-PadA)") (class "Default")
      (node (ref "D1") (pin "A") (pinfunction "A_A") (pintype "passive"))
      (node (ref "R2") (pin "1") (pinfunction "1_1") (pintype "passive"))
    )
    (net (code "36") (name "Net-(LCD1-LED_K1)") (class "Default")
      (node (ref "LCD1") (pin "P$11") (pinfunction "LED_K1_P$11") (pintype "bidirectional"))
      (node (ref "LCD1") (pin "P$12") (pinfunction "LED_K2_P$12") (pintype "bidirectional"))
      (node (ref "LCD1") (pin "P$13") (pinfunction "LED_K3_P$13") (pintype "bidirectional"))
      (node (ref "LCD1") (pin "P$14") (pinfunction "LED_K4_P$14") (pintype "bidirectional"))
      (node (ref "R19") (pin "1") (pinfunction "1_1") (pintype "passive"))
    )
    (net (code "37") (name "Net-(PAM84031-INL)") (class "Default")
      (node (ref "PAM84031") (pin "7") (pinfunction "INL_7") (pintype "input"))
      (node (ref "R38") (pin "2") (pinfunction "2_2") (pintype "passive"))
    )
    (net (code "38") (name "Net-(PAM84031-VREF)") (class "Default")
      (node (ref "C17") (pin "2") (pinfunction "2_2") (pintype "passive"))
      (node (ref "PAM84031") (pin "8") (pinfunction "VREF_8") (pintype "input"))
    )
    (net (code "39") (name "Net-(S13-O)") (class "Default")
      (node (ref "R26") (pin "2") (pinfunction "2_2") (pintype "passive"))
      (node (ref "S13") (pin "1") (pinfunction "O_1") (pintype "passive"))
      (node (ref "U2") (pin "3") (pinfunction "EN_3") (pintype "input"))
    )
    (net (code "40") (name "Net-(T1-B)") (class "Default")
      (node (ref "R8") (pin "1") (pinfunction "1_1") (pintype "passive"))
      (node (ref "T1") (pin "1") (pinfunction "B_1") (pintype "passive"))
    )
    (net (code "41") (name "Net-(T2-B)") (class "Default")
      (node (ref "R9") (pin "1") (pinfunction "1_1") (pintype "passive"))
      (node (ref "T2") (pin "1") (pinfunction "B_1") (pintype "passive"))
    )
    (net (code "42") (name "Net-(T3-C)") (class "Default")
      (node (ref "R19") (pin "2") (pinfunction "2_2") (pintype "passive"))
      (node (ref "T3") (pin "3") (pinfunction "C_3") (pintype "passive"))
    )
    (net (code "43") (name "Net-(U2-BP)") (class "Default")
      (node (ref "C6") (pin "1") (pinfunction "1_1") (pintype "passive"))
      (node (ref "U2") (pin "4") (pinfunction "BP_4") (pintype "input"))
    )
    (net (code "44") (name "Net-(U3-PROG)") (class "Default")
      (node (ref "R27") (pin "2") (pinfunction "2_2") (pintype "passive"))
      (node (ref "U3") (pin "5") (pinfunction "PROG_5") (pintype "input"))
    )
    (net (code "45") (name "Net-(U4-XI)") (class "Default")
      (node (ref "U4") (pin "7") (pinfunction "XI_7") (pintype "bidirectional"))
      (node (ref "Y1") (pin "3") (pinfunction "2_3") (pintype "passive"))
    )
    (net (code "46") (name "Net-(U4-XO)") (class "Default")
      (node (ref "U4") (pin "8") (pinfunction "XO_8") (pintype "bidirectional"))
      (node (ref "Y1") (pin "1") (pinfunction "1_1") (pintype "passive"))
    )
    (net (code "47") (name "Net-(U5-DEEM{slash}CLKOUT)") (class "Default")
      (node (ref "R35") (pin "2") (pinfunction "2_2") (pintype "passive"))
      (node (ref "U5") (pin "9") (pinfunction "DEEM/CLKOUT_9") (pintype "bidirectional"))
    )
    (net (code "48") (name "Net-(U5-MUTE)") (class "Default")
      (node (ref "R34") (pin "2") (pinfunction "2_2") (pintype "passive"))
      (node (ref "U5") (pin "8") (pinfunction "MUTE_8") (pintype "input"))
    )
    (net (code "49") (name "Net-(U5-PLL0)") (class "Default")
      (node (ref "R36") (pin "2") (pinfunction "2_2") (pintype "passive"))
      (node (ref "U5") (pin "10") (pinfunction "PLL0_10") (pintype "input"))
    )
    (net (code "50") (name "Net-(U5-SFOR0)") (class "Default")
      (node (ref "R33") (pin "2") (pinfunction "2_2") (pintype "passive"))
      (node (ref "U5") (pin "11") (pinfunction "SFOR0_11") (pintype "input"))
    )
    (net (code "51") (name "Net-(U5-SFOR1)") (class "Default")
      (node (ref "R31") (pin "2") (pinfunction "2_2") (pintype "passive"))
      (node (ref "U5") (pin "7") (pinfunction "SFOR1_7") (pintype "input"))
    )
    (net (code "52") (name "Net-(U5-SYSCLK{slash}PLL1)") (class "Default")
      (node (ref "R30") (pin "2") (pinfunction "2_2") (pintype "passive"))
      (node (ref "U5") (pin "6") (pinfunction "SYSCLK/PLL1_6") (pintype "input"))
    )
    (net (code "53") (name "Net-(U5-VREF(DAC))") (class "Default")
      (node (ref "C20") (pin "2") (pinfunction "2_2") (pintype "passive"))
      (node (ref "C21") (pin "2") (pinfunction "2_2") (pintype "passive"))
      (node (ref "U5") (pin "12") (pinfunction "VREF(DAC)_12") (pintype "output"))
    )
    (net (code "54") (name "RDAC") (class "Default")
      (node (ref "C24") (pin "2") (pinfunction "2_2") (pintype "passive"))
      (node (ref "J5") (pin "TIP") (pinfunction "TIP_TIP") (pintype "bidirectional"))
      (node (ref "R42") (pin "2") (pinfunction "2_2") (pintype "passive"))
    )
    (net (code "55") (name "RESET") (class "Default")
      (node (ref "A1") (pin "3") (pinfunction "EN_3") (pintype "input"))
      (node (ref "C1") (pin "1") (pinfunction "1_1") (pintype "passive"))
      (node (ref "LCD1") (pin "P$2") (pinfunction "RESET_P$2") (pintype "bidirectional"))
      (node (ref "R1") (pin "1") (pinfunction "1_1") (pintype "passive"))
      (node (ref "S1") (pin "3") (pinfunction "2_3") (pintype "passive"))
      (node (ref "S1") (pin "4") (pinfunction "2_4") (pintype "passive"))
      (node (ref "T1") (pin "3") (pinfunction "C_3") (pintype "passive"))
    )
    (net (code "56") (name "RIGHT") (class "Default")
      (node (ref "R13") (pin "2") (pinfunction "2_2") (pintype "passive"))
      (node (ref "S5") (pin "3") (pinfunction "3_3") (pintype "passive"))
      (node (ref "U1") (pin "10") (pinfunction "P5_10") (pintype "bidirectional"))
    )
    (net (code "57") (name "RTS") (class "Default")
      (node (ref "R9") (pin "2") (pinfunction "2_2") (pintype "passive"))
      (node (ref "T1") (pin "2") (pinfunction "E_2") (pintype "passive"))
      (node (ref "U4") (pin "14") (pinfunction "~{RTS}_14") (pintype "bidirectional"))
    )
    (net (code "58") (name "RX") (class "Default")
      (node (ref "A1") (pin "35") (pinfunction "TXD0_35") (pintype "bidirectional"))
      (node (ref "U4") (pin "3") (pinfunction "RXI_3") (pintype "bidirectional"))
    )
    (net (code "59") (name "R_BTN") (class "Default")
      (node (ref "A1") (pin "6") (pinfunction "IO34_6") (pintype "input"))
      (node (ref "R22") (pin "2") (pinfunction "2_2") (pintype "passive"))
      (node (ref "S12") (pin "1") (pinfunction "1_1") (pintype "passive"))
    )
    (net (code "60") (name "SD_CLK") (class "Default")
      (node (ref "A1") (pin "13") (pinfunction "IO14_13") (pintype "bidirectional"))
      (node (ref "J1") (pin "5") (pinfunction "CLK_5") (pintype "bidirectional"))
      (node (ref "R4") (pin "2") (pinfunction "2_2") (pintype "passive"))
      (node (ref "U7") (pin "1") (pinfunction "1_1") (pintype "bidirectional"))
    )
    (net (code "61") (name "SD_CMD") (class "Default")
      (node (ref "A1") (pin "23") (pinfunction "IO15_23") (pintype "bidirectional"))
      (node (ref "J1") (pin "3") (pinfunction "CMD_DIN_3") (pintype "bidirectional"))
      (node (ref "R5") (pin "2") (pinfunction "2_2") (pintype "passive"))
      (node (ref "U8") (pin "1") (pinfunction "1_1") (pintype "bidirectional"))
    )
    (net (code "62") (name "SD_DAT0") (class "Default")
      (node (ref "A1") (pin "24") (pinfunction "IO2_24") (pintype "bidirectional"))
      (node (ref "J1") (pin "7") (pinfunction "DAT0_DO_7") (pintype "bidirectional"))
      (node (ref "JP1") (pin "1") (pinfunction "1_1") (pintype "passive"))
      (node (ref "R3") (pin "2") (pinfunction "2_2") (pintype "passive"))
      (node (ref "U6") (pin "1") (pinfunction "1_1") (pintype "bidirectional"))
    )
    (net (code "63") (name "SELECT") (class "Default")
      (node (ref "R15") (pin "2") (pinfunction "2_2") (pintype "passive"))
      (node (ref "S7") (pin "3") (pinfunction "3_3") (pintype "passive"))
      (node (ref "U1") (pin "5") (pinfunction "P1_5") (pintype "bidirectional"))
    )
    (net (code "64") (name "SPK+") (class "Default")
      (node (ref "JP2") (pin "2") (pinfunction "2_2") (pintype "passive"))
      (node (ref "PAM84031") (pin "1") (pinfunction "+OUT_L_1") (pintype "input"))
    )
    (net (code "65") (name "SPK-") (class "Default")
      (node (ref "JP2") (pin "1") (pinfunction "1_1") (pintype "passive"))
      (node (ref "PAM84031") (pin "3") (pinfunction "-OUT_L_3") (pintype "input"))
    )
    (net (code "66") (name "START") (class "Default")
      (node (ref "R14") (pin "2") (pinfunction "2_2") (pintype "passive"))
      (node (ref "S6") (pin "3") (pinfunction "3_3") (pintype "passive"))
      (node (ref "U1") (pin "4") (pinfunction "P0_4") (pintype "bidirectional"))
    )
    (net (code "67") (name "TX") (class "Default")
      (node (ref "A1") (pin "34") (pinfunction "RXD0_34") (pintype "bidirectional"))
      (node (ref "U4") (pin "2") (pinfunction "TXO_2") (pintype "bidirectional"))
    )
    (net (code "68") (name "UP") (class "Default")
      (node (ref "R10") (pin "2") (pinfunction "2_2") (pintype "passive"))
      (node (ref "S2") (pin "3") (pinfunction "3_3") (pintype "passive"))
      (node (ref "U1") (pin "6") (pinfunction "P2_6") (pintype "bidirectional"))
    )
    (net (code "69") (name "USB_DET") (class "Default")
      (node (ref "A1") (pin "8") (pinfunction "IO32_8") (pintype "bidirectional"))
      (node (ref "R24") (pin "2") (pinfunction "2_2") (pintype "passive"))
      (node (ref "R25") (pin "2") (pinfunction "2_2") (pintype "passive"))
    )
    (net (code "70") (name "VBAT_S") (class "Default")
      (node (ref "A1") (pin "5") (pinfunction "SENSOR_VN_5") (pintype "input"))
      (node (ref "C9") (pin "1") (pinfunction "1_1") (pintype "passive"))
      (node (ref "R28") (pin "2") (pinfunction "2_2") (pintype "passive"))
      (node (ref "R29") (pin "1") (pinfunction "1_1") (pintype "passive"))
    )
    (net (code "71") (name "VIN") (class "Default")
      (node (ref "C14") (pin "2") (pinfunction "2_2") (pintype "passive"))
      (node (ref "C15") (pin "2") (pinfunction "2_2") (pintype "passive"))
      (node (ref "C16") (pin "2") (pinfunction "2_2") (pintype "passive"))
      (node (ref "C25") (pin "2") (pinfunction "2_2") (pintype "passive"))
      (node (ref "C26") (pin "2") (pinfunction "2_2") (pintype "passive"))
      (node (ref "D2") (pin "C") (pinfunction "C_C") (pintype "passive"))
      (node (ref "PAM84031") (pin "13") (pinfunction "PVDD1_13") (pintype "output"))
      (node (ref "PAM84031") (pin "4") (pinfunction "PVDD_4") (pintype "input"))
      (node (ref "PAM84031") (pin "5") (pinfunction "MUTE_5") (pintype "input"))
      (node (ref "PAM84031") (pin "6") (pinfunction "VDD_6") (pintype "input"))
      (node (ref "Q1") (pin "2") (pinfunction "S_2") (pintype "bidirectional"))
      (node (ref "S13") (pin "2") (pinfunction "P_2") (pintype "passive"))
      (node (ref "U2") (pin "1") (pinfunction "IN_1") (pintype "input"))
    )
    (net (code "72") (name "V_BATT") (class "Default")
      (node (ref "C8") (pin "1") (pinfunction "1_1") (pintype "passive"))
      (node (ref "J4") (pin "2") (pinfunction "+_2") (pintype "bidirectional"))
      (node (ref "Q1") (pin "3") (pinfunction "D_3") (pintype "bidirectional"))
      (node (ref "R28") (pin "1") (pinfunction "1_1") (pintype "passive"))
      (node (ref "TP2") (pin "P$1") (pinfunction "1_P$1") (pintype "bidirectional"))
      (node (ref "U3") (pin "3") (pinfunction "BAT_3") (pintype "output"))
    )
    (net (code "73") (name "V_USB") (class "Default")
      (node (ref "C5") (pin "2") (pinfunction "2_2") (pintype "passive"))
      (node (ref "D2") (pin "A") (pinfunction "A_A") (pintype "passive"))
      (node (ref "J3") (pin "VBUS") (pinfunction "VBUS_VBUS") (pintype "power_in"))
      (node (ref "Q1") (pin "1") (pinfunction "G_1") (pintype "bidirectional"))
      (node (ref "R23") (pin "2") (pinfunction "2_2") (pintype "passive"))
      (node (ref "R24") (pin "1") (pinfunction "1_1") (pintype "passive"))
      (node (ref "TP1") (pin "P$1") (pinfunction "1_P$1") (pintype "bidirectional"))
      (node (ref "U3") (pin "4") (pinfunction "VCC_4") (pintype "power_in"))
    )
    (net (code "74") (name "unconnected-(A1-SCK{slash}CLK-Pad20)") (class "Default")
      (node (ref "A1") (pin "20") (pinfunction "SCK/CLK_20") (pintype "bidirectional"))
    )
    (net (code "75") (name "unconnected-(A1-SCS{slash}CMD-Pad19)") (class "Default")
      (node (ref "A1") (pin "19") (pinfunction "SCS/CMD_19") (pintype "bidirectional"))
    )
    (net (code "76") (name "unconnected-(A1-SDI{slash}SD1-Pad22)") (class "Default")
      (node (ref "A1") (pin "22") (pinfunction "SDI/SD1_22") (pintype "bidirectional"))
    )
    (net (code "77") (name "unconnected-(A1-SDO{slash}SD0-Pad21)") (class "Default")
      (node (ref "A1") (pin "21") (pinfunction "SDO/SD0_21") (pintype "bidirectional"))
    )
    (net (code "78") (name "unconnected-(A1-SHD{slash}SD2-Pad17)") (class "Default")
      (node (ref "A1") (pin "17") (pinfunction "SHD/SD2_17") (pintype "bidirectional"))
    )
    (net (code "79") (name "unconnected-(A1-SWP{slash}SD3-Pad18)") (class "Default")
      (node (ref "A1") (pin "18") (pinfunction "SWP/SD3_18") (pintype "bidirectional"))
    )
    (net (code "80") (name "unconnected-(J1-CD_DAT3_CS-Pad2)") (class "Default")
      (node (ref "J1") (pin "2") (pinfunction "CD_DAT3_CS_2") (pintype "bidirectional"))
    )
    (net (code "81") (name "unconnected-(J1-DAT1-Pad8)") (class "Default")
      (node (ref "J1") (pin "8") (pinfunction "DAT1_8") (pintype "bidirectional"))
    )
    (net (code "82") (name "unconnected-(J1-DAT2-Pad1)") (class "Default")
      (node (ref "J1") (pin "1") (pinfunction "DAT2_1") (pintype "bidirectional"))
    )
    (net (code "83") (name "unconnected-(J1-PadCD)") (class "Default")
      (node (ref "J1") (pin "CD") (pinfunction "CD_CD") (pintype "bidirectional"))
    )
    (net (code "84") (name "unconnected-(J3-PadID)") (class "Default")
      (node (ref "J3") (pin "ID") (pinfunction "ID_ID") (pintype "bidirectional"))
    )
    (net (code "85") (name "unconnected-(J4-PAD1-PadNC1)") (class "Default")
      (node (ref "J4") (pin "NC1") (pinfunction "PAD1_NC1") (pintype "bidirectional"))
    )
    (net (code "86") (name "unconnected-(J4-PAD2-PadNC2)") (class "Default")
      (node (ref "J4") (pin "NC2") (pinfunction "PAD2_NC2") (pintype "bidirectional"))
    )
    (net (code "87") (name "unconnected-(J5-PadTSH)") (class "Default")
      (node (ref "J5") (pin "TSH") (pinfunction "TSH_TSH") (pintype "bidirectional"))
    )
    (net (code "88") (name "unconnected-(LCD1-SDO-PadP$7)") (class "Default")
      (node (ref "LCD1") (pin "P$7") (pinfunction "SDO_P$7") (pintype "bidirectional"))
    )
    (net (code "89") (name "unconnected-(LCD1-XL-PadP$15)") (class "Default")
      (node (ref "LCD1") (pin "P$15") (pinfunction "XL_P$15") (pintype "bidirectional"))
    )
    (net (code "90") (name "unconnected-(LCD1-XR-PadP$17)") (class "Default")
      (node (ref "LCD1") (pin "P$17") (pinfunction "XR_P$17") (pintype "bidirectional"))
    )
    (net (code "91") (name "unconnected-(LCD1-YD-PadP$18)") (class "Default")
      (node (ref "LCD1") (pin "P$18") (pinfunction "YD_P$18") (pintype "bidirectional"))
    )
    (net (code "92") (name "unconnected-(LCD1-YU-PadP$16)") (class "Default")
      (node (ref "LCD1") (pin "P$16") (pinfunction "YU_P$16") (pintype "bidirectional"))
    )
    (net (code "93") (name "unconnected-(PAM84031-+OUT_R-Pad16)") (class "Default")
      (node (ref "PAM84031") (pin "16") (pinfunction "+OUT_R_16") (pintype "output"))
    )
    (net (code "94") (name "unconnected-(PAM84031--OUT_R-Pad14)") (class "Default")
      (node (ref "PAM84031") (pin "14") (pinfunction "-OUT_R_14") (pintype "output"))
    )
    (net (code "95") (name "unconnected-(PAM84031-INR-Pad10)") (class "Default")
      (node (ref "PAM84031") (pin "10") (pinfunction "INR_10") (pintype "output"))
    )
    (net (code "96") (name "unconnected-(PAM84031-NC-Pad9)") (class "Default")
      (node (ref "PAM84031") (pin "9") (pinfunction "NC_9") (pintype "output"))
    )
    (net (code "97") (name "unconnected-(S2-Pad4)") (class "Default")
      (node (ref "S2") (pin "4") (pinfunction "4_4") (pintype "passive"))
    )
    (net (code "98") (name "unconnected-(S3-Pad4)") (class "Default")
      (node (ref "S3") (pin "4") (pinfunction "4_4") (pintype "passive"))
    )
    (net (code "99") (name "unconnected-(S4-Pad4)") (class "Default")
      (node (ref "S4") (pin "4") (pinfunction "4_4") (pintype "passive"))
    )
    (net (code "100") (name "unconnected-(S5-Pad4)") (class "Default")
      (node (ref "S5") (pin "4") (pinfunction "4_4") (pintype "passive"))
    )
    (net (code "101") (name "unconnected-(S6-Pad4)") (class "Default")
      (node (ref "S6") (pin "4") (pinfunction "4_4") (pintype "passive"))
    )
    (net (code "102") (name "unconnected-(S7-Pad4)") (class "Default")
      (node (ref "S7") (pin "4") (pinfunction "4_4") (pintype "passive"))
    )
    (net (code "103") (name "unconnected-(S8-Pad4)") (class "Default")
      (node (ref "S8") (pin "4") (pinfunction "4_4") (pintype "passive"))
    )
    (net (code "104") (name "unconnected-(S9-Pad4)") (class "Default")
      (node (ref "S9") (pin "4") (pinfunction "4_4") (pintype "passive"))
    )
    (net (code "105") (name "unconnected-(S11-Pad2)") (class "Default")
      (node (ref "S11") (pin "2") (pinfunction "2_2") (pintype "passive"))
    )
    (net (code "106") (name "unconnected-(S13-S-Pad3)") (class "Default")
      (node (ref "S13") (pin "3") (pinfunction "S_3") (pintype "passive"))
    )
    (net (code "107") (name "unconnected-(U1-_INT-Pad13)") (class "Default")
      (node (ref "U1") (pin "13") (pinfunction "_INT_13") (pintype "bidirectional"))
    )
    (net (code "108") (name "unconnected-(U4-R232-Pad15)") (class "Default")
      (node (ref "U4") (pin "15") (pinfunction "R232_15") (pintype "bidirectional"))
    )
    (net (code "109") (name "unconnected-(U4-~{CTS}-Pad9)") (class "Default")
      (node (ref "U4") (pin "9") (pinfunction "~{CTS}_9") (pintype "bidirectional"))
    )
    (net (code "110") (name "unconnected-(U4-~{DCD}-Pad12)") (class "Default")
      (node (ref "U4") (pin "12") (pinfunction "~{DCD}_12") (pintype "bidirectional"))
    )
    (net (code "111") (name "unconnected-(U4-~{DSR}-Pad10)") (class "Default")
      (node (ref "U4") (pin "10") (pinfunction "~{DSR}_10") (pintype "bidirectional"))
    )
    (net (code "112") (name "unconnected-(U4-~{RI}-Pad11)") (class "Default")
      (node (ref "U4") (pin "11") (pinfunction "~{RI}_11") (pintype "bidirectional"))
    )
  )
)
